# top.net
KiCad netlist of a schematic drawn in EAGLE
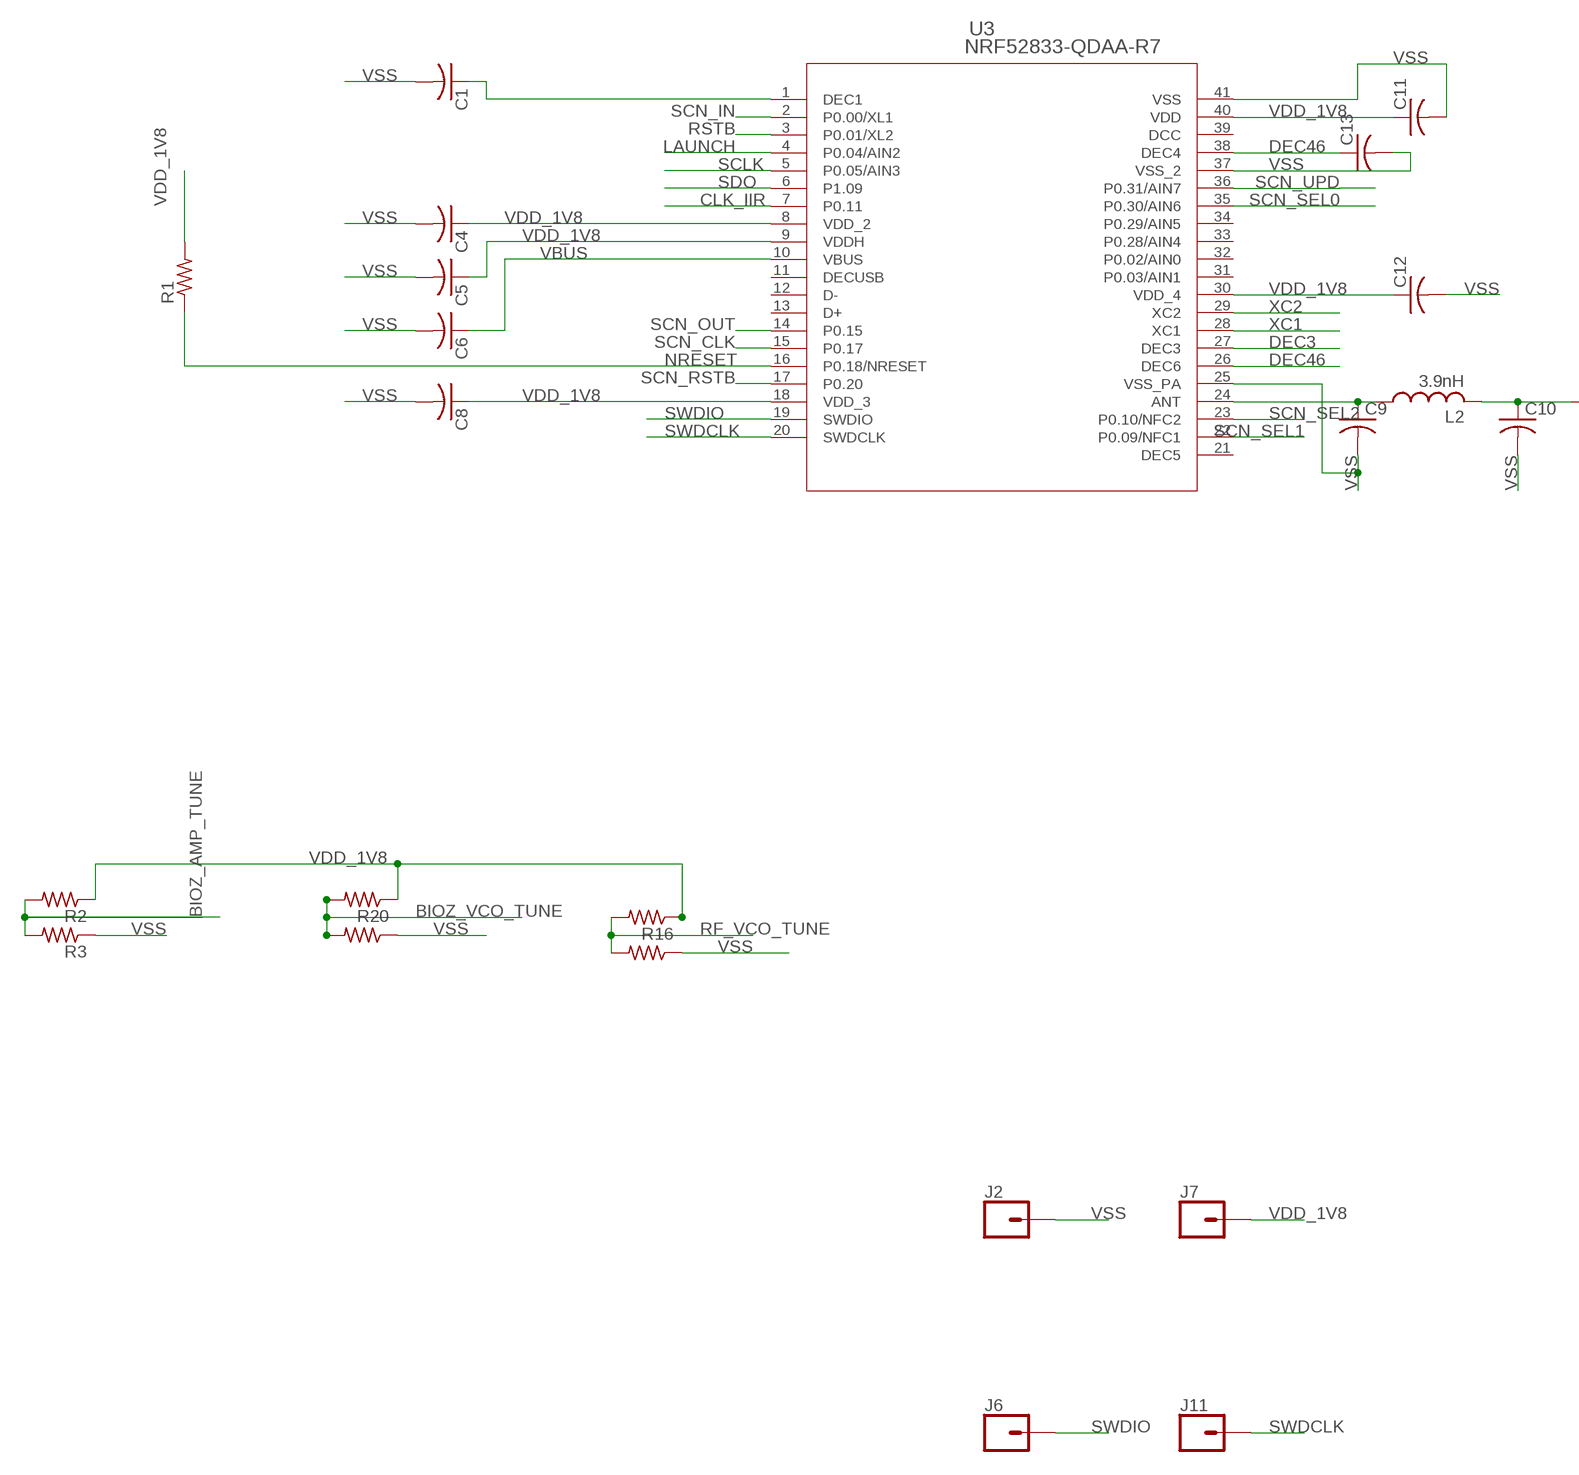
[diagram p0: schematic, sheet 1, part 1 of 2]
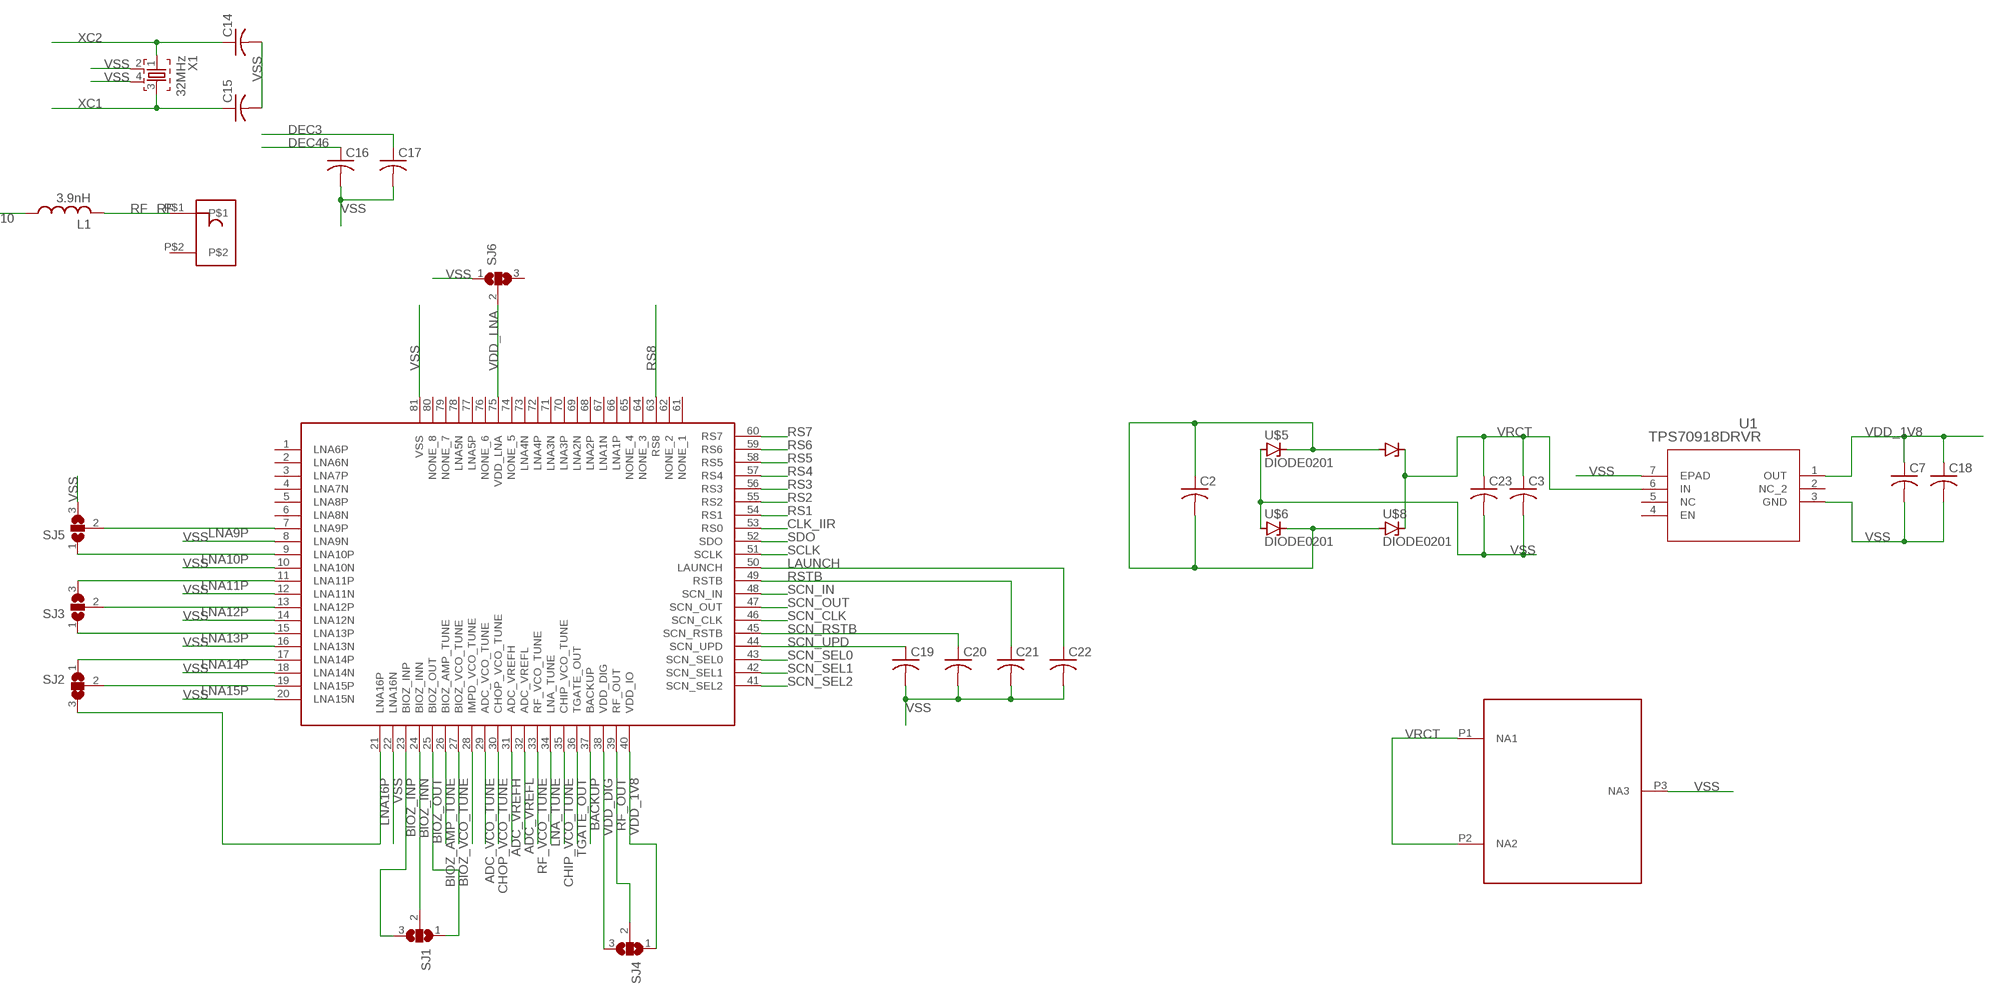
[diagram p1: schematic, sheet 1, part 2 of 2]

(export (version "E")
  (design (tool "Eeschema 10.0.6"))
  (components
    (comp (ref "C1")
      (value "C-USC0201")
      (footprint "eagle-import:C0201")
      (libsource (lib "eagle-import") (part "rcl_334_C-USC0201"))
    )
    (comp (ref "C2")
      (value "C-USC0201")
      (footprint "eagle-import:C0201")
      (libsource (lib "eagle-import") (part "rcl_334_C-USC0201"))
    )
    (comp (ref "C3")
      (value "C-USC0402")
      (footprint "eagle-import:C0402")
      (libsource (lib "eagle-import") (part "rcl_334_C-USC0402"))
    )
    (comp (ref "C4")
      (value "C-USC0201")
      (footprint "eagle-import:C0201")
      (libsource (lib "eagle-import") (part "rcl_334_C-USC0201"))
    )
    (comp (ref "C5")
      (value "C-USC0201")
      (footprint "eagle-import:C0201")
      (libsource (lib "eagle-import") (part "rcl_334_C-USC0201"))
    )
    (comp (ref "C6")
      (value "C-USC0201")
      (footprint "eagle-import:C0201")
      (libsource (lib "eagle-import") (part "rcl_334_C-USC0201"))
    )
    (comp (ref "C7")
      (value "C-USC1210")
      (footprint "eagle-import:C1210")
      (libsource (lib "eagle-import") (part "C-USC1210"))
    )
    (comp (ref "C8")
      (value "C-USC0201")
      (footprint "eagle-import:C0201")
      (libsource (lib "eagle-import") (part "rcl_334_C-USC0201"))
    )
    (comp (ref "C9")
      (value "C-USC0201")
      (footprint "eagle-import:C0201")
      (libsource (lib "eagle-import") (part "rcl_334_C-USC0201"))
    )
    (comp (ref "C10")
      (value "C-USC0201")
      (footprint "eagle-import:C0201")
      (libsource (lib "eagle-import") (part "rcl_334_C-USC0201"))
    )
    (comp (ref "C11")
      (value "C-USC0201")
      (footprint "eagle-import:C0201")
      (libsource (lib "eagle-import") (part "rcl_334_C-USC0201"))
    )
    (comp (ref "C12")
      (value "C-USC0201")
      (footprint "eagle-import:C0201")
      (libsource (lib "eagle-import") (part "rcl_334_C-USC0201"))
    )
    (comp (ref "C13")
      (value "C-USC0201")
      (footprint "eagle-import:C0201")
      (libsource (lib "eagle-import") (part "rcl_334_C-USC0201"))
    )
    (comp (ref "C14")
      (value "C-USC0201")
      (footprint "eagle-import:C0201")
      (libsource (lib "eagle-import") (part "rcl_334_C-USC0201"))
    )
    (comp (ref "C15")
      (value "C-USC0201")
      (footprint "eagle-import:C0201")
      (libsource (lib "eagle-import") (part "rcl_334_C-USC0201"))
    )
    (comp (ref "C16")
      (value "C-USC0201")
      (footprint "eagle-import:C0201")
      (libsource (lib "eagle-import") (part "rcl_334_C-USC0201"))
    )
    (comp (ref "C17")
      (value "C-USC0201")
      (footprint "eagle-import:C0201")
      (libsource (lib "eagle-import") (part "rcl_334_C-USC0201"))
    )
    (comp (ref "C18")
      (value "C-USC0402")
      (footprint "eagle-import:C0402")
      (libsource (lib "eagle-import") (part "rcl_334_C-USC0402"))
    )
    (comp (ref "C19")
      (value "C-USC0201")
      (footprint "eagle-import:C0201")
      (libsource (lib "eagle-import") (part "rcl_334_C-USC0201"))
    )
    (comp (ref "C20")
      (value "C-USC0201")
      (footprint "eagle-import:C0201")
      (libsource (lib "eagle-import") (part "rcl_334_C-USC0201"))
    )
    (comp (ref "C21")
      (value "C-USC0201")
      (footprint "eagle-import:C0201")
      (libsource (lib "eagle-import") (part "rcl_334_C-USC0201"))
    )
    (comp (ref "C22")
      (value "C-USC0201")
      (footprint "eagle-import:C0201")
      (libsource (lib "eagle-import") (part "rcl_334_C-USC0201"))
    )
    (comp (ref "C23")
      (value "C-USC1210")
      (footprint "eagle-import:C1210")
      (libsource (lib "eagle-import") (part "C-USC1210"))
    )
    (comp (ref "J2")
      (value "CONN_01")
      (footprint "eagle-import:1X01")
      (libsource (lib "eagle-import") (part "CONN_01"))
    )
    (comp (ref "J6")
      (value "CONN_01")
      (footprint "eagle-import:1X01")
      (libsource (lib "eagle-import") (part "CONN_01"))
    )
    (comp (ref "J7")
      (value "CONN_01")
      (footprint "eagle-import:1X01")
      (libsource (lib "eagle-import") (part "CONN_01"))
    )
    (comp (ref "J11")
      (value "CONN_01")
      (footprint "eagle-import:1X01")
      (libsource (lib "eagle-import") (part "CONN_01"))
    )
    (comp (ref "L1")
      (value "3.9nH")
      (footprint "eagle-import:RESC0402_N")
      (libsource (lib "eagle-import") (part "INDUCTOR_0402_N"))
    )
    (comp (ref "L2")
      (value "3.9nH")
      (footprint "eagle-import:RESC0402_N")
      (libsource (lib "eagle-import") (part "INDUCTOR_0402_N"))
    )
    (comp (ref "R1")
      (value "R-US_R0402")
      (footprint "eagle-import:R0402")
      (libsource (lib "eagle-import") (part "R-US_R0402"))
    )
    (comp (ref "R2")
      (value "R-US_R0201")
      (footprint "eagle-import:R0201")
      (libsource (lib "eagle-import") (part "R-US_R0201"))
    )
    (comp (ref "R3")
      (value "R-US_R0201")
      (footprint "eagle-import:R0201")
      (libsource (lib "eagle-import") (part "R-US_R0201"))
    )
    (comp (ref "R16")
      (value "R-US_R0201")
      (footprint "eagle-import:R0201")
      (libsource (lib "eagle-import") (part "R-US_R0201"))
    )
    (comp (ref "R17")
      (value "R-US_R0201")
      (footprint "eagle-import:R0201")
      (libsource (lib "eagle-import") (part "R-US_R0201"))
    )
    (comp (ref "R20")
      (value "R-US_R0201")
      (footprint "eagle-import:R0201")
      (libsource (lib "eagle-import") (part "R-US_R0201"))
    )
    (comp (ref "R22")
      (value "R-US_R0201")
      (footprint "eagle-import:R0201")
      (libsource (lib "eagle-import") (part "R-US_R0201"))
    )
    (comp (ref "SJ1")
      (value "SJ2W")
      (footprint "eagle-import:SJ_2")
      (libsource (lib "eagle-import") (part "SJ2W"))
    )
    (comp (ref "SJ2")
      (value "SJ2W")
      (footprint "eagle-import:SJ_2")
      (libsource (lib "eagle-import") (part "SJ2W"))
    )
    (comp (ref "SJ3")
      (value "SJ2W")
      (footprint "eagle-import:SJ_2")
      (libsource (lib "eagle-import") (part "SJ2W"))
    )
    (comp (ref "SJ4")
      (value "SJ2W")
      (footprint "eagle-import:SJ_2")
      (libsource (lib "eagle-import") (part "SJ2W"))
    )
    (comp (ref "SJ5")
      (value "SJ2W")
      (footprint "eagle-import:SJ_2")
      (libsource (lib "eagle-import") (part "SJ2W"))
    )
    (comp (ref "SJ6")
      (value "SJ2W")
      (footprint "eagle-import:SJ_2")
      (libsource (lib "eagle-import") (part "SJ2W"))
    )
    (comp (ref "U$1")
      (value "CHIP_QFN")
      (footprint "eagle-import:QFN50P1200X1200X80-81T900N")
      (libsource (lib "eagle-import") (part "CHIP_QFN"))
    )
    (comp (ref "U$3")
      (value "3030TR")
      (footprint "eagle-import:3030TR")
      (libsource (lib "eagle-import") (part "3030TR"))
    )
    (comp (ref "U$4")
      (value "AMCA31")
      (footprint "eagle-import:AMCA31")
      (libsource (lib "eagle-import") (part "AMCA31"))
    )
    (comp (ref "U$5")
      (value "DIODE0201")
      (footprint "eagle-import:C0201")
      (libsource (lib "eagle-import") (part "DIODE0201"))
    )
    (comp (ref "U$6")
      (value "DIODE0201")
      (footprint "eagle-import:C0201")
      (libsource (lib "eagle-import") (part "DIODE0201"))
    )
    (comp (ref "U$7")
      (value "DIODE0201")
      (footprint "eagle-import:C0201")
      (libsource (lib "eagle-import") (part "DIODE0201"))
    )
    (comp (ref "U$8")
      (value "DIODE0201")
      (footprint "eagle-import:C0201")
      (libsource (lib "eagle-import") (part "DIODE0201"))
    )
    (comp (ref "U1")
      (value "TPS70918DRVR")
      (footprint "eagle-import:DRV6_1P6X1_TEX")
      (fields (field (name "COPYRIGHT") "Copyright (C) 2023 Ultra Librarian. All rights reserved."))
      (libsource (lib "eagle-import") (part "TPS70918DRVR"))
    )
    (comp (ref "U3")
      (value "NRF52833-QDAA-R7")
      (footprint "eagle-import:QFN40_5X5_DQ_NOR")
      (fields (field (name "COPYRIGHT") "Copyright (C) 2023 Ultra Librarian. All rights reserved."))
      (libsource (lib "eagle-import") (part "NRF52833-QDAA-R7"))
    )
    (comp (ref "X1")
      (value "32MHz")
      (footprint "eagle-import:BT-XTAL_2016_N")
      (libsource (lib "eagle-import") (part "XTAL_32MHZ"))
    )
  )
  (nets
    (net (code "1") (name "/ADC_VCO_TUNE") (class "Default")
      (node (ref "U$1") (pin "29") (pinfunction "ADC_VCO_TUNE_29") (pintype "bidirectional"))
    )
    (net (code "2") (name "/ADC_VREFH") (class "Default")
      (node (ref "U$1") (pin "31") (pinfunction "ADC_VREFH_31") (pintype "bidirectional"))
    )
    (net (code "3") (name "/ADC_VREFL") (class "Default")
      (node (ref "U$1") (pin "32") (pinfunction "ADC_VREFL_32") (pintype "bidirectional"))
    )
    (net (code "4") (name "/BACKUP") (class "Default")
      (node (ref "U$1") (pin "37") (pinfunction "BACKUP_37") (pintype "bidirectional"))
    )
    (net (code "5") (name "/BIOZ_AMP_TUNE") (class "Default")
      (node (ref "R2") (pin "2") (pinfunction "2_2") (pintype "passive"))
      (node (ref "R3") (pin "2") (pinfunction "2_2") (pintype "passive"))
      (node (ref "U$1") (pin "26") (pinfunction "BIOZ_AMP_TUNE_26") (pintype "bidirectional"))
    )
    (net (code "6") (name "/BIOZ_INN") (class "Default")
      (node (ref "SJ1") (pin "2") (pinfunction "2_2") (pintype "passive"))
      (node (ref "U$1") (pin "24") (pinfunction "BIOZ_INN_24") (pintype "bidirectional"))
    )
    (net (code "7") (name "/BIOZ_INP") (class "Default")
      (node (ref "SJ1") (pin "3") (pinfunction "3_3") (pintype "passive"))
      (node (ref "U$1") (pin "23") (pinfunction "BIOZ_INP_23") (pintype "bidirectional"))
    )
    (net (code "8") (name "/BIOZ_OUT") (class "Default")
      (node (ref "SJ1") (pin "1") (pinfunction "1_1") (pintype "passive"))
      (node (ref "U$1") (pin "25") (pinfunction "BIOZ_OUT_25") (pintype "bidirectional"))
    )
    (net (code "9") (name "/BIOZ_VCO_TUNE") (class "Default")
      (node (ref "R20") (pin "2") (pinfunction "2_2") (pintype "passive"))
      (node (ref "R22") (pin "2") (pinfunction "2_2") (pintype "passive"))
      (node (ref "U$1") (pin "27") (pinfunction "BIOZ_VCO_TUNE_27") (pintype "bidirectional"))
    )
    (net (code "10") (name "/CHIP_VCO_TUNE") (class "Default")
      (node (ref "U$1") (pin "35") (pinfunction "CHIP_VCO_TUNE_35") (pintype "bidirectional"))
    )
    (net (code "11") (name "/CHOP_VCO_TUNE") (class "Default")
      (node (ref "U$1") (pin "30") (pinfunction "CHOP_VCO_TUNE_30") (pintype "bidirectional"))
    )
    (net (code "12") (name "/CLK_IIR") (class "Default")
      (node (ref "U$1") (pin "53") (pinfunction "RS0_53") (pintype "bidirectional"))
      (node (ref "U3") (pin "7") (pinfunction "P0.11_7") (pintype "bidirectional"))
    )
    (net (code "13") (name "/DCC") (class "Default")
      (node (ref "U3") (pin "39") (pinfunction "DCC_39") (pintype "power_in"))
    )
    (net (code "14") (name "/DEC3") (class "Default")
      (node (ref "C17") (pin "1") (pinfunction "1_1") (pintype "passive"))
      (node (ref "U3") (pin "27") (pinfunction "DEC3_27") (pintype "power_in"))
    )
    (net (code "15") (name "/DEC5") (class "Default")
      (node (ref "U3") (pin "21") (pinfunction "DEC5_21") (pintype "power_in"))
    )
    (net (code "16") (name "/DEC46") (class "Default")
      (node (ref "C13") (pin "1") (pinfunction "1_1") (pintype "passive"))
      (node (ref "C16") (pin "1") (pinfunction "1_1") (pintype "passive"))
      (node (ref "U3") (pin "26") (pinfunction "DEC6_26") (pintype "power_in"))
      (node (ref "U3") (pin "38") (pinfunction "DEC4_38") (pintype "power_in"))
    )
    (net (code "17") (name "/DECUSB") (class "Default")
      (node (ref "U3") (pin "11") (pinfunction "DECUSB_11") (pintype "power_in"))
    )
    (net (code "18") (name "/LAUNCH") (class "Default")
      (node (ref "C22") (pin "1") (pinfunction "1_1") (pintype "passive"))
      (node (ref "U$1") (pin "50") (pinfunction "LAUNCH_50") (pintype "bidirectional"))
      (node (ref "U3") (pin "4") (pinfunction "P0.04/AIN2_4") (pintype "bidirectional"))
    )
    (net (code "19") (name "/LNA9P") (class "Default")
      (node (ref "SJ5") (pin "2") (pinfunction "2_2") (pintype "passive"))
      (node (ref "U$1") (pin "7") (pinfunction "LNA9P_7") (pintype "bidirectional"))
    )
    (net (code "20") (name "/LNA10P") (class "Default")
      (node (ref "SJ5") (pin "1") (pinfunction "1_1") (pintype "passive"))
      (node (ref "U$1") (pin "9") (pinfunction "LNA10P_9") (pintype "bidirectional"))
    )
    (net (code "21") (name "/LNA11P") (class "Default")
      (node (ref "SJ3") (pin "3") (pinfunction "3_3") (pintype "passive"))
      (node (ref "U$1") (pin "11") (pinfunction "LNA11P_11") (pintype "bidirectional"))
    )
    (net (code "22") (name "/LNA12P") (class "Default")
      (node (ref "SJ3") (pin "2") (pinfunction "2_2") (pintype "passive"))
      (node (ref "U$1") (pin "13") (pinfunction "LNA12P_13") (pintype "bidirectional"))
    )
    (net (code "23") (name "/LNA13P") (class "Default")
      (node (ref "SJ3") (pin "1") (pinfunction "1_1") (pintype "passive"))
      (node (ref "U$1") (pin "15") (pinfunction "LNA13P_15") (pintype "bidirectional"))
    )
    (net (code "24") (name "/LNA14P") (class "Default")
      (node (ref "SJ2") (pin "1") (pinfunction "1_1") (pintype "passive"))
      (node (ref "U$1") (pin "17") (pinfunction "LNA14P_17") (pintype "bidirectional"))
    )
    (net (code "25") (name "/LNA15P") (class "Default")
      (node (ref "SJ2") (pin "2") (pinfunction "2_2") (pintype "passive"))
      (node (ref "U$1") (pin "19") (pinfunction "LNA15P_19") (pintype "bidirectional"))
    )
    (net (code "26") (name "/LNA16P") (class "Default")
      (node (ref "SJ2") (pin "3") (pinfunction "3_3") (pintype "passive"))
      (node (ref "U$1") (pin "21") (pinfunction "LNA16P_21") (pintype "bidirectional"))
    )
    (net (code "27") (name "/LNA_TUNE") (class "Default")
      (node (ref "U$1") (pin "34") (pinfunction "LNA_TUNE_34") (pintype "bidirectional"))
    )
    (net (code "28") (name "/NRESET") (class "Default")
      (node (ref "R1") (pin "1") (pinfunction "1_1") (pintype "passive"))
      (node (ref "U3") (pin "16") (pinfunction "P0.18/NRESET_16") (pintype "bidirectional"))
    )
    (net (code "29") (name "/RF") (class "Default")
      (node (ref "L1") (pin "2") (pinfunction "2_2") (pintype "passive"))
      (node (ref "U$4") (pin "P$1") (pinfunction "P$1_P$1") (pintype "bidirectional"))
    )
    (net (code "30") (name "/RF_OUT") (class "Default")
      (node (ref "SJ4") (pin "2") (pinfunction "2_2") (pintype "passive"))
      (node (ref "U$1") (pin "39") (pinfunction "RF_OUT_39") (pintype "bidirectional"))
    )
    (net (code "31") (name "/RF_VCO_TUNE") (class "Default")
      (node (ref "R16") (pin "2") (pinfunction "2_2") (pintype "passive"))
      (node (ref "R17") (pin "2") (pinfunction "2_2") (pintype "passive"))
      (node (ref "U$1") (pin "33") (pinfunction "RF_VCO_TUNE_33") (pintype "bidirectional"))
    )
    (net (code "32") (name "/RS1") (class "Default")
      (node (ref "U$1") (pin "54") (pinfunction "RS1_54") (pintype "bidirectional"))
    )
    (net (code "33") (name "/RS2") (class "Default")
      (node (ref "U$1") (pin "55") (pinfunction "RS2_55") (pintype "bidirectional"))
    )
    (net (code "34") (name "/RS3") (class "Default")
      (node (ref "U$1") (pin "56") (pinfunction "RS3_56") (pintype "bidirectional"))
    )
    (net (code "35") (name "/RS4") (class "Default")
      (node (ref "U$1") (pin "57") (pinfunction "RS4_57") (pintype "bidirectional"))
    )
    (net (code "36") (name "/RS5") (class "Default")
      (node (ref "U$1") (pin "58") (pinfunction "RS5_58") (pintype "bidirectional"))
    )
    (net (code "37") (name "/RS6") (class "Default")
      (node (ref "U$1") (pin "59") (pinfunction "RS6_59") (pintype "bidirectional"))
    )
    (net (code "38") (name "/RS7") (class "Default")
      (node (ref "U$1") (pin "60") (pinfunction "RS7_60") (pintype "bidirectional"))
    )
    (net (code "39") (name "/RS8") (class "Default")
      (node (ref "U$1") (pin "63") (pinfunction "RS8_63") (pintype "bidirectional"))
    )
    (net (code "40") (name "/RSTB") (class "Default")
      (node (ref "C21") (pin "1") (pinfunction "1_1") (pintype "passive"))
      (node (ref "U$1") (pin "49") (pinfunction "RSTB_49") (pintype "bidirectional"))
      (node (ref "U3") (pin "3") (pinfunction "P0.01/XL2_3") (pintype "bidirectional"))
    )
    (net (code "41") (name "/SCLK") (class "Default")
      (node (ref "U$1") (pin "51") (pinfunction "SCLK_51") (pintype "bidirectional"))
      (node (ref "U3") (pin "5") (pinfunction "P0.05/AIN3_5") (pintype "bidirectional"))
    )
    (net (code "42") (name "/SCN_CLK") (class "Default")
      (node (ref "U$1") (pin "46") (pinfunction "SCN_CLK_46") (pintype "bidirectional"))
      (node (ref "U3") (pin "15") (pinfunction "P0.17_15") (pintype "bidirectional"))
    )
    (net (code "43") (name "/SCN_IN") (class "Default")
      (node (ref "U$1") (pin "48") (pinfunction "SCN_IN_48") (pintype "bidirectional"))
      (node (ref "U3") (pin "2") (pinfunction "P0.00/XL1_2") (pintype "bidirectional"))
    )
    (net (code "44") (name "/SCN_OUT") (class "Default")
      (node (ref "U$1") (pin "47") (pinfunction "SCN_OUT_47") (pintype "bidirectional"))
      (node (ref "U3") (pin "14") (pinfunction "P0.15_14") (pintype "bidirectional"))
    )
    (net (code "45") (name "/SCN_RSTB") (class "Default")
      (node (ref "C20") (pin "1") (pinfunction "1_1") (pintype "passive"))
      (node (ref "U$1") (pin "45") (pinfunction "SCN_RSTB_45") (pintype "bidirectional"))
      (node (ref "U3") (pin "17") (pinfunction "P0.20_17") (pintype "bidirectional"))
    )
    (net (code "46") (name "/SCN_SEL0") (class "Default")
      (node (ref "U$1") (pin "43") (pinfunction "SCN_SEL0_43") (pintype "bidirectional"))
      (node (ref "U3") (pin "35") (pinfunction "P0.30/AIN6_35") (pintype "bidirectional"))
    )
    (net (code "47") (name "/SCN_SEL1") (class "Default")
      (node (ref "U$1") (pin "42") (pinfunction "SCN_SEL1_42") (pintype "bidirectional"))
      (node (ref "U3") (pin "22") (pinfunction "P0.09/NFC1_22") (pintype "bidirectional"))
    )
    (net (code "48") (name "/SCN_SEL2") (class "Default")
      (node (ref "U$1") (pin "41") (pinfunction "SCN_SEL2_41") (pintype "bidirectional"))
      (node (ref "U3") (pin "23") (pinfunction "P0.10/NFC2_23") (pintype "bidirectional"))
    )
    (net (code "49") (name "/SCN_UPD") (class "Default")
      (node (ref "C19") (pin "1") (pinfunction "1_1") (pintype "passive"))
      (node (ref "U$1") (pin "44") (pinfunction "SCN_UPD_44") (pintype "bidirectional"))
      (node (ref "U3") (pin "36") (pinfunction "P0.31/AIN7_36") (pintype "bidirectional"))
    )
    (net (code "50") (name "/SDO") (class "Default")
      (node (ref "U$1") (pin "52") (pinfunction "SDO_52") (pintype "bidirectional"))
      (node (ref "U3") (pin "6") (pinfunction "P1.09_6") (pintype "bidirectional"))
    )
    (net (code "51") (name "/SWDCLK") (class "Default")
      (node (ref "J11") (pin "1") (pinfunction "1_1") (pintype "passive"))
      (node (ref "U3") (pin "20") (pinfunction "SWDCLK_20") (pintype "input"))
    )
    (net (code "52") (name "/SWDIO") (class "Default")
      (node (ref "J6") (pin "1") (pinfunction "1_1") (pintype "passive"))
      (node (ref "U3") (pin "19") (pinfunction "SWDIO_19") (pintype "bidirectional"))
    )
    (net (code "53") (name "/TGATE_OUT") (class "Default")
      (node (ref "U$1") (pin "36") (pinfunction "TGATE_OUT_36") (pintype "bidirectional"))
    )
    (net (code "54") (name "/VBUS") (class "Default")
      (node (ref "C6") (pin "1") (pinfunction "1_1") (pintype "passive"))
      (node (ref "U3") (pin "10") (pinfunction "VBUS_10") (pintype "power_in"))
    )
    (net (code "55") (name "/VDD_1V8") (class "Default")
      (node (ref "C11") (pin "1") (pinfunction "1_1") (pintype "passive"))
      (node (ref "C12") (pin "1") (pinfunction "1_1") (pintype "passive"))
      (node (ref "C18") (pin "1") (pinfunction "1_1") (pintype "passive"))
      (node (ref "C4") (pin "1") (pinfunction "1_1") (pintype "passive"))
      (node (ref "C5") (pin "1") (pinfunction "1_1") (pintype "passive"))
      (node (ref "C7") (pin "1") (pinfunction "1_1") (pintype "passive"))
      (node (ref "C8") (pin "1") (pinfunction "1_1") (pintype "passive"))
      (node (ref "J7") (pin "1") (pinfunction "1_1") (pintype "passive"))
      (node (ref "R1") (pin "2") (pinfunction "2_2") (pintype "passive"))
      (node (ref "R16") (pin "1") (pinfunction "1_1") (pintype "passive"))
      (node (ref "R2") (pin "1") (pinfunction "1_1") (pintype "passive"))
      (node (ref "R20") (pin "1") (pinfunction "1_1") (pintype "passive"))
      (node (ref "SJ4") (pin "1") (pinfunction "1_1") (pintype "passive"))
      (node (ref "U$1") (pin "40") (pinfunction "VDD_IO_40") (pintype "bidirectional"))
      (node (ref "U1") (pin "1") (pinfunction "OUT_1") (pintype "output"))
      (node (ref "U3") (pin "18") (pinfunction "VDD_3_18") (pintype "power_in"))
      (node (ref "U3") (pin "30") (pinfunction "VDD_4_30") (pintype "power_in"))
      (node (ref "U3") (pin "40") (pinfunction "VDD_40") (pintype "power_in"))
      (node (ref "U3") (pin "8") (pinfunction "VDD_2_8") (pintype "power_in"))
      (node (ref "U3") (pin "9") (pinfunction "VDDH_9") (pintype "power_in"))
    )
    (net (code "56") (name "/VDD_DIG") (class "Default")
      (node (ref "SJ4") (pin "3") (pinfunction "3_3") (pintype "passive"))
      (node (ref "U$1") (pin "38") (pinfunction "VDD_DIG_38") (pintype "bidirectional"))
    )
    (net (code "57") (name "/VDD_LNA") (class "Default")
      (node (ref "SJ6") (pin "2") (pinfunction "2_2") (pintype "passive"))
      (node (ref "U$1") (pin "75") (pinfunction "VDD_LNA_75") (pintype "bidirectional"))
    )
    (net (code "58") (name "/VRCT") (class "Default")
      (node (ref "C23") (pin "1") (pinfunction "1_1") (pintype "passive"))
      (node (ref "C3") (pin "1") (pinfunction "1_1") (pintype "passive"))
      (node (ref "U$3") (pin "P1") (pinfunction "NA1_P1") (pintype "bidirectional"))
      (node (ref "U$3") (pin "P2") (pinfunction "NA2_P2") (pintype "bidirectional"))
      (node (ref "U$7") (pin "2") (pinfunction "C_2") (pintype "passive"))
      (node (ref "U$8") (pin "2") (pinfunction "C_2") (pintype "passive"))
      (node (ref "U1") (pin "6") (pinfunction "IN_6") (pintype "input"))
    )
    (net (code "59") (name "/VSS") (class "Default")
      (node (ref "C1") (pin "2") (pinfunction "2_2") (pintype "passive"))
      (node (ref "C10") (pin "2") (pinfunction "2_2") (pintype "passive"))
      (node (ref "C11") (pin "2") (pinfunction "2_2") (pintype "passive"))
      (node (ref "C12") (pin "2") (pinfunction "2_2") (pintype "passive"))
      (node (ref "C13") (pin "2") (pinfunction "2_2") (pintype "passive"))
      (node (ref "C14") (pin "2") (pinfunction "2_2") (pintype "passive"))
      (node (ref "C15") (pin "2") (pinfunction "2_2") (pintype "passive"))
      (node (ref "C16") (pin "2") (pinfunction "2_2") (pintype "passive"))
      (node (ref "C17") (pin "2") (pinfunction "2_2") (pintype "passive"))
      (node (ref "C18") (pin "2") (pinfunction "2_2") (pintype "passive"))
      (node (ref "C19") (pin "2") (pinfunction "2_2") (pintype "passive"))
      (node (ref "C20") (pin "2") (pinfunction "2_2") (pintype "passive"))
      (node (ref "C21") (pin "2") (pinfunction "2_2") (pintype "passive"))
      (node (ref "C22") (pin "2") (pinfunction "2_2") (pintype "passive"))
      (node (ref "C23") (pin "2") (pinfunction "2_2") (pintype "passive"))
      (node (ref "C3") (pin "2") (pinfunction "2_2") (pintype "passive"))
      (node (ref "C4") (pin "2") (pinfunction "2_2") (pintype "passive"))
      (node (ref "C5") (pin "2") (pinfunction "2_2") (pintype "passive"))
      (node (ref "C6") (pin "2") (pinfunction "2_2") (pintype "passive"))
      (node (ref "C7") (pin "2") (pinfunction "2_2") (pintype "passive"))
      (node (ref "C8") (pin "2") (pinfunction "2_2") (pintype "passive"))
      (node (ref "C9") (pin "2") (pinfunction "2_2") (pintype "passive"))
      (node (ref "J2") (pin "1") (pinfunction "1_1") (pintype "passive"))
      (node (ref "R17") (pin "1") (pinfunction "1_1") (pintype "passive"))
      (node (ref "R22") (pin "1") (pinfunction "1_1") (pintype "passive"))
      (node (ref "R3") (pin "1") (pinfunction "1_1") (pintype "passive"))
      (node (ref "SJ5") (pin "3") (pinfunction "3_3") (pintype "passive"))
      (node (ref "SJ6") (pin "1") (pinfunction "1_1") (pintype "passive"))
      (node (ref "U$1") (pin "10") (pinfunction "LNA10N_10") (pintype "bidirectional"))
      (node (ref "U$1") (pin "12") (pinfunction "LNA11N_12") (pintype "bidirectional"))
      (node (ref "U$1") (pin "14") (pinfunction "LNA12N_14") (pintype "bidirectional"))
      (node (ref "U$1") (pin "16") (pinfunction "LNA13N_16") (pintype "bidirectional"))
      (node (ref "U$1") (pin "18") (pinfunction "LNA14N_18") (pintype "bidirectional"))
      (node (ref "U$1") (pin "20") (pinfunction "LNA15N_20") (pintype "bidirectional"))
      (node (ref "U$1") (pin "22") (pinfunction "LNA16N_22") (pintype "bidirectional"))
      (node (ref "U$1") (pin "8") (pinfunction "LNA9N_8") (pintype "bidirectional"))
      (node (ref "U$1") (pin "81") (pinfunction "VSS_81") (pintype "bidirectional"))
      (node (ref "U$3") (pin "P3") (pinfunction "NA3_P3") (pintype "bidirectional"))
      (node (ref "U$5") (pin "1") (pinfunction "A_1") (pintype "passive"))
      (node (ref "U$6") (pin "1") (pinfunction "A_1") (pintype "passive"))
      (node (ref "U1") (pin "3") (pinfunction "GND_3") (pintype "power_in"))
      (node (ref "U1") (pin "7") (pinfunction "EPAD_7") (pintype "passive"))
      (node (ref "U3") (pin "25") (pinfunction "VSS_PA_25") (pintype "passive"))
      (node (ref "U3") (pin "37") (pinfunction "VSS_2_37") (pintype "passive"))
      (node (ref "U3") (pin "41") (pinfunction "VSS_41") (pintype "passive"))
      (node (ref "X1") (pin "2") (pinfunction "2_2") (pintype "passive"))
      (node (ref "X1") (pin "4") (pinfunction "4_4") (pintype "passive"))
    )
    (net (code "60") (name "/XC1") (class "Default")
      (node (ref "C15") (pin "1") (pinfunction "1_1") (pintype "passive"))
      (node (ref "U3") (pin "28") (pinfunction "XC1_28") (pintype "input"))
      (node (ref "X1") (pin "3") (pinfunction "3_3") (pintype "passive"))
    )
    (net (code "61") (name "/XC2") (class "Default")
      (node (ref "C14") (pin "1") (pinfunction "1_1") (pintype "passive"))
      (node (ref "U3") (pin "29") (pinfunction "XC2_29") (pintype "input"))
      (node (ref "X1") (pin "1") (pinfunction "1_1") (pintype "passive"))
    )
    (net (code "62") (name "Net-(C10-Pad1)") (class "Default")
      (node (ref "C10") (pin "1") (pinfunction "1_1") (pintype "passive"))
      (node (ref "L1") (pin "1") (pinfunction "1_1") (pintype "passive"))
      (node (ref "L2") (pin "2") (pinfunction "2_2") (pintype "passive"))
    )
    (net (code "63") (name "Net-(U$5-C)") (class "Default")
      (node (ref "C2") (pin "1") (pinfunction "1_1") (pintype "passive"))
      (node (ref "C2") (pin "2") (pinfunction "2_2") (pintype "passive"))
      (node (ref "U$5") (pin "2") (pinfunction "C_2") (pintype "passive"))
      (node (ref "U$6") (pin "2") (pinfunction "C_2") (pintype "passive"))
      (node (ref "U$7") (pin "1") (pinfunction "A_1") (pintype "passive"))
      (node (ref "U$8") (pin "1") (pinfunction "A_1") (pintype "passive"))
    )
    (net (code "64") (name "Net-(U3-ANT)") (class "Default")
      (node (ref "C9") (pin "1") (pinfunction "1_1") (pintype "passive"))
      (node (ref "L2") (pin "1") (pinfunction "1_1") (pintype "passive"))
      (node (ref "U3") (pin "24") (pinfunction "ANT_24") (pintype "passive"))
    )
    (net (code "65") (name "Net-(U3-DEC1)") (class "Default")
      (node (ref "C1") (pin "1") (pinfunction "1_1") (pintype "passive"))
      (node (ref "U3") (pin "1") (pinfunction "DEC1_1") (pintype "power_in"))
    )
    (net (code "66") (name "unconnected-(SJ6-Pad3)") (class "Default")
      (node (ref "SJ6") (pin "3") (pinfunction "3_3") (pintype "passive"))
    )
    (net (code "67") (name "unconnected-(U$1-IMPD_VCO_TUNE-Pad28)") (class "Default")
      (node (ref "U$1") (pin "28") (pinfunction "IMPD_VCO_TUNE_28") (pintype "bidirectional"))
    )
    (net (code "68") (name "unconnected-(U$1-LNA1N-Pad67)") (class "Default")
      (node (ref "U$1") (pin "67") (pinfunction "LNA1N_67") (pintype "bidirectional"))
    )
    (net (code "69") (name "unconnected-(U$1-LNA1P-Pad66)") (class "Default")
      (node (ref "U$1") (pin "66") (pinfunction "LNA1P_66") (pintype "bidirectional"))
    )
    (net (code "70") (name "unconnected-(U$1-LNA2N-Pad69)") (class "Default")
      (node (ref "U$1") (pin "69") (pinfunction "LNA2N_69") (pintype "bidirectional"))
    )
    (net (code "71") (name "unconnected-(U$1-LNA2P-Pad68)") (class "Default")
      (node (ref "U$1") (pin "68") (pinfunction "LNA2P_68") (pintype "bidirectional"))
    )
    (net (code "72") (name "unconnected-(U$1-LNA3N-Pad71)") (class "Default")
      (node (ref "U$1") (pin "71") (pinfunction "LNA3N_71") (pintype "bidirectional"))
    )
    (net (code "73") (name "unconnected-(U$1-LNA3P-Pad70)") (class "Default")
      (node (ref "U$1") (pin "70") (pinfunction "LNA3P_70") (pintype "bidirectional"))
    )
    (net (code "74") (name "unconnected-(U$1-LNA4N-Pad73)") (class "Default")
      (node (ref "U$1") (pin "73") (pinfunction "LNA4N_73") (pintype "bidirectional"))
    )
    (net (code "75") (name "unconnected-(U$1-LNA4P-Pad72)") (class "Default")
      (node (ref "U$1") (pin "72") (pinfunction "LNA4P_72") (pintype "bidirectional"))
    )
    (net (code "76") (name "unconnected-(U$1-LNA5N-Pad78)") (class "Default")
      (node (ref "U$1") (pin "78") (pinfunction "LNA5N_78") (pintype "bidirectional"))
    )
    (net (code "77") (name "unconnected-(U$1-LNA5P-Pad77)") (class "Default")
      (node (ref "U$1") (pin "77") (pinfunction "LNA5P_77") (pintype "bidirectional"))
    )
    (net (code "78") (name "unconnected-(U$1-LNA6N-Pad2)") (class "Default")
      (node (ref "U$1") (pin "2") (pinfunction "LNA6N_2") (pintype "bidirectional"))
    )
    (net (code "79") (name "unconnected-(U$1-LNA6P-Pad1)") (class "Default")
      (node (ref "U$1") (pin "1") (pinfunction "LNA6P_1") (pintype "bidirectional"))
    )
    (net (code "80") (name "unconnected-(U$1-LNA7N-Pad4)") (class "Default")
      (node (ref "U$1") (pin "4") (pinfunction "LNA7N_4") (pintype "bidirectional"))
    )
    (net (code "81") (name "unconnected-(U$1-LNA7P-Pad3)") (class "Default")
      (node (ref "U$1") (pin "3") (pinfunction "LNA7P_3") (pintype "bidirectional"))
    )
    (net (code "82") (name "unconnected-(U$1-LNA8N-Pad6)") (class "Default")
      (node (ref "U$1") (pin "6") (pinfunction "LNA8N_6") (pintype "bidirectional"))
    )
    (net (code "83") (name "unconnected-(U$1-LNA8P-Pad5)") (class "Default")
      (node (ref "U$1") (pin "5") (pinfunction "LNA8P_5") (pintype "bidirectional"))
    )
    (net (code "84") (name "unconnected-(U$1-NONE_1-Pad61)") (class "Default")
      (node (ref "U$1") (pin "61") (pinfunction "NONE_1_61") (pintype "bidirectional"))
    )
    (net (code "85") (name "unconnected-(U$1-NONE_2-Pad62)") (class "Default")
      (node (ref "U$1") (pin "62") (pinfunction "NONE_2_62") (pintype "bidirectional"))
    )
    (net (code "86") (name "unconnected-(U$1-NONE_3-Pad64)") (class "Default")
      (node (ref "U$1") (pin "64") (pinfunction "NONE_3_64") (pintype "bidirectional"))
    )
    (net (code "87") (name "unconnected-(U$1-NONE_4-Pad65)") (class "Default")
      (node (ref "U$1") (pin "65") (pinfunction "NONE_4_65") (pintype "bidirectional"))
    )
    (net (code "88") (name "unconnected-(U$1-NONE_5-Pad74)") (class "Default")
      (node (ref "U$1") (pin "74") (pinfunction "NONE_5_74") (pintype "bidirectional"))
    )
    (net (code "89") (name "unconnected-(U$1-NONE_6-Pad76)") (class "Default")
      (node (ref "U$1") (pin "76") (pinfunction "NONE_6_76") (pintype "bidirectional"))
    )
    (net (code "90") (name "unconnected-(U$1-NONE_7-Pad79)") (class "Default")
      (node (ref "U$1") (pin "79") (pinfunction "NONE_7_79") (pintype "bidirectional"))
    )
    (net (code "91") (name "unconnected-(U$1-NONE_8-Pad80)") (class "Default")
      (node (ref "U$1") (pin "80") (pinfunction "NONE_8_80") (pintype "bidirectional"))
    )
    (net (code "92") (name "unconnected-(U$4-PadP$2)") (class "Default")
      (node (ref "U$4") (pin "P$2") (pinfunction "P$2_P$2") (pintype "bidirectional"))
    )
    (net (code "93") (name "unconnected-(U1-EN-Pad4)") (class "Default")
      (node (ref "U1") (pin "4") (pinfunction "EN_4") (pintype "input"))
    )
    (net (code "94") (name "unconnected-(U1-NC-Pad5)") (class "Default")
      (node (ref "U1") (pin "5") (pinfunction "NC_5") (pintype "no_connect"))
    )
    (net (code "95") (name "unconnected-(U1-NC_2-Pad2)") (class "Default")
      (node (ref "U1") (pin "2") (pinfunction "NC_2_2") (pintype "no_connect"))
    )
    (net (code "96") (name "unconnected-(U3-D+-Pad13)") (class "Default")
      (node (ref "U3") (pin "13") (pinfunction "D+_13") (pintype "bidirectional"))
    )
    (net (code "97") (name "unconnected-(U3-D--Pad12)") (class "Default")
      (node (ref "U3") (pin "12") (pinfunction "D-_12") (pintype "bidirectional"))
    )
    (net (code "98") (name "unconnected-(U3-P0.02{slash}AIN0-Pad32)") (class "Default")
      (node (ref "U3") (pin "32") (pinfunction "P0.02/AIN0_32") (pintype "bidirectional"))
    )
    (net (code "99") (name "unconnected-(U3-P0.03{slash}AIN1-Pad31)") (class "Default")
      (node (ref "U3") (pin "31") (pinfunction "P0.03/AIN1_31") (pintype "bidirectional"))
    )
    (net (code "100") (name "unconnected-(U3-P0.28{slash}AIN4-Pad33)") (class "Default")
      (node (ref "U3") (pin "33") (pinfunction "P0.28/AIN4_33") (pintype "bidirectional"))
    )
    (net (code "101") (name "unconnected-(U3-P0.29{slash}AIN5-Pad34)") (class "Default")
      (node (ref "U3") (pin "34") (pinfunction "P0.29/AIN5_34") (pintype "bidirectional"))
    )
  )
)
